# REGULADOR_5V_y_9V.net
KiCad netlist of a schematic drawn in EAGLE
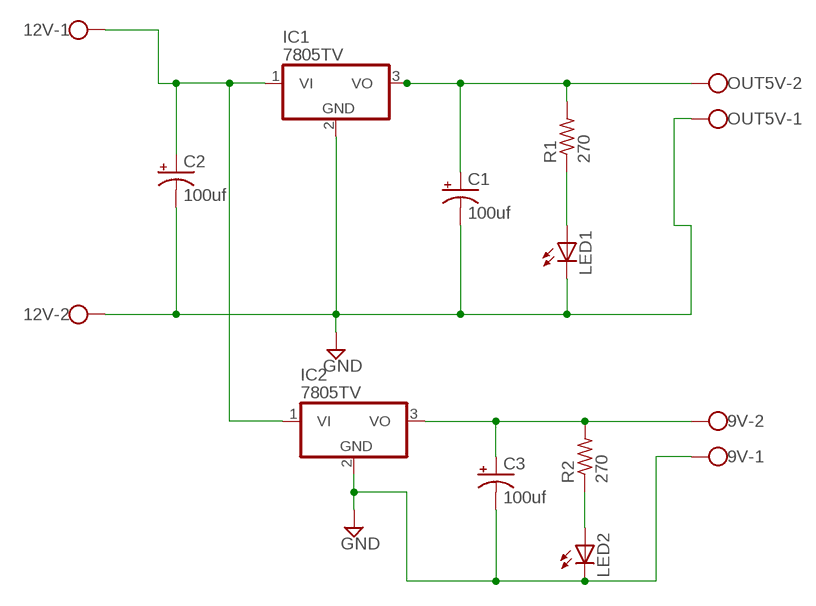
[diagram p0: schematic, sheet 1]

(export (version "E")
  (design (tool "Eeschema 10.0.6"))
  (components
    (comp (ref "9V")
      (value "W237-102")
      (footprint "eagle-import:W237-102")
      (fields (field (name "MPN") "237-102"))
      (libsource (lib "eagle-import") (part "W237-102"))
    )
    (comp (ref "12V")
      (value "W237-102")
      (footprint "eagle-import:W237-102")
      (fields (field (name "MPN") "237-102"))
      (libsource (lib "eagle-import") (part "W237-102"))
    )
    (comp (ref "C1")
      (value "100uf")
      (footprint "eagle-import:E2,5-5")
      (libsource (lib "eagle-import") (part "CPOL-USE2.5-5"))
    )
    (comp (ref "C2")
      (value "100uf")
      (footprint "eagle-import:E2,5-5")
      (libsource (lib "eagle-import") (part "CPOL-USE2.5-5"))
    )
    (comp (ref "C3")
      (value "100uf")
      (footprint "eagle-import:E2,5-5")
      (libsource (lib "eagle-import") (part "CPOL-USE2.5-5"))
    )
    (comp (ref "IC1")
      (value "7805TV")
      (footprint "eagle-import:TO220V")
      (libsource (lib "eagle-import") (part "78TV05"))
    )
    (comp (ref "IC2")
      (value "7805TV")
      (footprint "eagle-import:TO220V")
      (libsource (lib "eagle-import") (part "78TV05"))
    )
    (comp (ref "LED1")
      (value "LED5MM")
      (footprint "eagle-import:LED5MM")
      (libsource (lib "eagle-import") (part "LED5MM"))
    )
    (comp (ref "LED2")
      (value "LED5MM")
      (footprint "eagle-import:LED5MM")
      (libsource (lib "eagle-import") (part "LED5MM"))
    )
    (comp (ref "OUT5V")
      (value "W237-102")
      (footprint "eagle-import:W237-102")
      (fields (field (name "MPN") "237-102"))
      (libsource (lib "eagle-import") (part "W237-102"))
    )
    (comp (ref "R1")
      (value "270")
      (footprint "eagle-import:0204_7")
      (libsource (lib "eagle-import") (part "R-US_0204/7"))
    )
    (comp (ref "R2")
      (value "270")
      (footprint "eagle-import:0204_7")
      (libsource (lib "eagle-import") (part "R-US_0204/7"))
    )
  )
  (nets
    (net (code "1") (name "GND") (class "Default")
      (node (ref "12V") (pin "2") (pinfunction "KL_2") (pintype "passive"))
      (node (ref "9V") (pin "1") (pinfunction "KL_1") (pintype "passive"))
      (node (ref "C1") (pin "-") (pinfunction "-_-") (pintype "passive"))
      (node (ref "C2") (pin "-") (pinfunction "-_-") (pintype "passive"))
      (node (ref "C3") (pin "-") (pinfunction "-_-") (pintype "passive"))
      (node (ref "IC1") (pin "2") (pinfunction "GND_2") (pintype "passive"))
      (node (ref "IC2") (pin "2") (pinfunction "GND_2") (pintype "passive"))
      (node (ref "LED1") (pin "K") (pinfunction "C_K") (pintype "passive"))
      (node (ref "LED2") (pin "K") (pinfunction "C_K") (pintype "passive"))
      (node (ref "OUT5V") (pin "1") (pinfunction "KL_1") (pintype "passive"))
    )
    (net (code "2") (name "Net-(9VB-KL)") (class "Default")
      (node (ref "9V") (pin "2") (pinfunction "KL_2") (pintype "passive"))
      (node (ref "C3") (pin "+") (pinfunction "+_+") (pintype "passive"))
      (node (ref "IC2") (pin "3") (pinfunction "VO_3") (pintype "passive"))
      (node (ref "R2") (pin "2") (pinfunction "2_2") (pintype "passive"))
    )
    (net (code "3") (name "Net-(12VA-KL)") (class "Default")
      (node (ref "12V") (pin "1") (pinfunction "KL_1") (pintype "passive"))
      (node (ref "C2") (pin "+") (pinfunction "+_+") (pintype "passive"))
      (node (ref "IC1") (pin "1") (pinfunction "VI_1") (pintype "input"))
      (node (ref "IC2") (pin "1") (pinfunction "VI_1") (pintype "input"))
    )
    (net (code "4") (name "Net-(IC1-VO)") (class "Default")
      (node (ref "C1") (pin "+") (pinfunction "+_+") (pintype "passive"))
      (node (ref "IC1") (pin "3") (pinfunction "VO_3") (pintype "passive"))
      (node (ref "OUT5V") (pin "2") (pinfunction "KL_2") (pintype "passive"))
      (node (ref "R1") (pin "2") (pinfunction "2_2") (pintype "passive"))
    )
    (net (code "5") (name "Net-(LED1-PadA)") (class "Default")
      (node (ref "LED1") (pin "A") (pinfunction "A_A") (pintype "passive"))
      (node (ref "R1") (pin "1") (pinfunction "1_1") (pintype "passive"))
    )
    (net (code "6") (name "Net-(LED2-PadA)") (class "Default")
      (node (ref "LED2") (pin "A") (pinfunction "A_A") (pintype "passive"))
      (node (ref "R2") (pin "1") (pinfunction "1_1") (pintype "passive"))
    )
  )
)
